# Main.net
KiCad netlist of a schematic drawn in Altium Designer
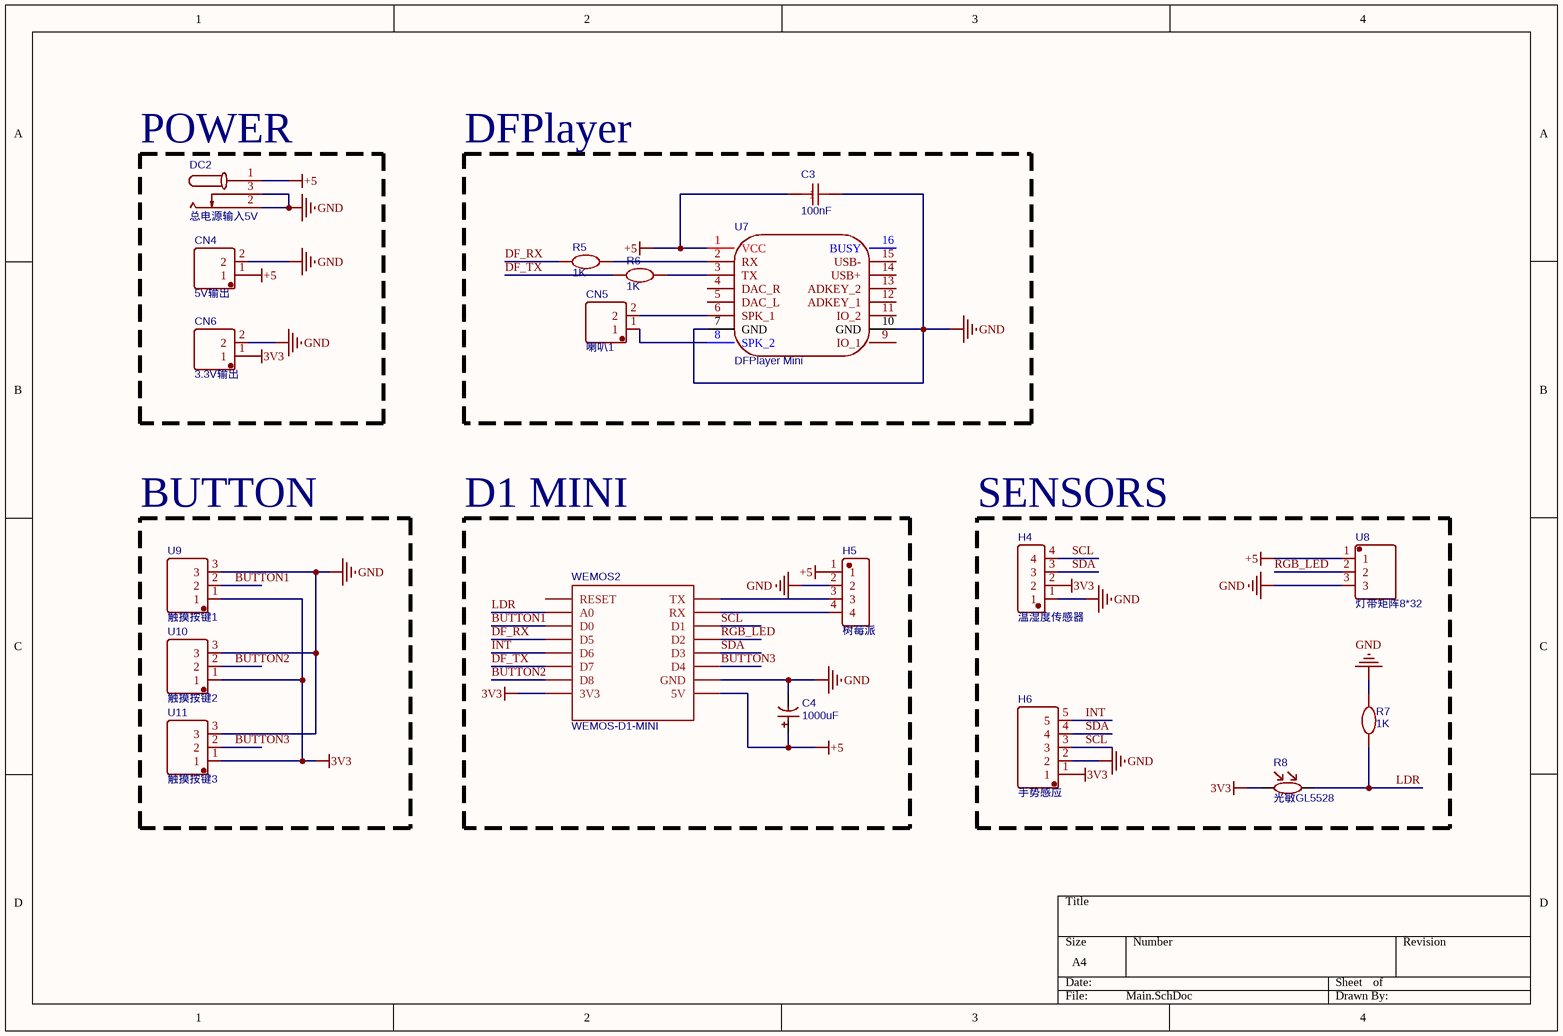
[diagram p0: Main.SchDoc]

(export (version "E")
  (design (tool "Eeschema 10.0.6"))
  (components
    (comp (ref "C3")
      (value "100nF")
      (footprint "CAP-SMD_BD6.3-L6.6-W6.6-LS7.2-FD")
      (fields
        (field (name "BOM_SUPPLIER PART") "C386152")
        (field (name "BOM_MANUFACTURER PART") "UMK107B104KAHT")
        (field (name "CONTRIBUTOR") "LCSC")
      )
      (libsource (lib "Connecter") (part "100nF"))
    )
    (comp (ref "C4")
      (value "1000uF")
      (footprint "1000uf25v")
      (fields (field (name "BOM_MANUFACTURER PART") "1000uF 16V") (field (name "BOM_SUPPLIER PART") "C43909"))
      (libsource (lib "Connecter") (part "1000uF"))
    )
    (comp (ref "CN4")
      (value "5V输出")
      (footprint "HDR-TH_2P-P2.54-V")
      (fields (field (name "BOM_SUPPLIER PART") "C160332") (field (name "CONTRIBUTOR") "LCSC"))
      (libsource (lib "Connecter") (part "5V输出"))
    )
    (comp (ref "CN5")
      (value "喇叭1")
      (footprint "HDR-TH_2P-P2.54-V")
      (fields (field (name "BOM_SUPPLIER PART") "C160332") (field (name "CONTRIBUTOR") "LCSC"))
      (libsource (lib "Connecter") (part "喇叭1"))
    )
    (comp (ref "CN6")
      (value "3.3V输出")
      (footprint "HDR-TH_2P-P2.54-V")
      (fields (field (name "BOM_SUPPLIER PART") "C160332") (field (name "CONTRIBUTOR") "LCSC"))
      (libsource (lib "Connecter") (part "3.3V输出"))
    )
    (comp (ref "DC2")
      (value "总电源输入5V")
      (footprint "DC-IN-TH_DC005")
      (fields (field (name "BOM_SUPPLIER PART") "C132516") (field (name "CONTRIBUTOR") "LCSC"))
      (libsource (lib "Connecter") (part "总电源输入5V"))
    )
    (comp (ref "H4")
      (value "温湿度传感器")
      (footprint "HDR-TH_4P-P2.54-V")
      (fields
        (field (name "BOM_MANUFACTURER PART") "Z-211-0411-0021-001")
        (field (name "BOM_SUPPLIER PART") "C152150")
        (field (name "CONTRIBUTOR") "LCSC")
      )
      (libsource (lib "Connecter") (part "i2C"))
    )
    (comp (ref "H5")
      (value "树莓派")
      (footprint "HDR-TH_4P-P2.54-V")
      (fields
        (field (name "BOM_MANUFACTURER PART") "Z-211-0411-0021-001")
        (field (name "BOM_SUPPLIER PART") "C152150")
        (field (name "CONTRIBUTOR") "LCSC")
      )
      (libsource (lib "Connecter") (part "树莓派"))
    )
    (comp (ref "H6")
      (value "手势感应")
      (footprint "HDR-TH_5P-P2.54-V")
      (fields
        (field (name "BOM_SUPPLIER PART") "C180219")
        (field (name "BOM_MANUFACTURER PART") "77311-462K05LF")
        (field (name "CONTRIBUTOR") "LCSC")
      )
      (libsource (lib "Connecter") (part "手势感应"))
    )
    (comp (ref "R5")
      (value "1K")
      (footprint "0805_R")
      (fields
        (field (name "BOM_SUPPLIER PART") "C433503")
        (field (name "BOM_MANUFACTURER PART") "RN 1/8W 1K F T/B A1")
        (field (name "CONTRIBUTOR") "LCSC")
      )
      (libsource (lib "Connecter") (part "1K"))
    )
    (comp (ref "R6")
      (value "1K")
      (footprint "0805_R")
      (fields
        (field (name "BOM_SUPPLIER PART") "C433503")
        (field (name "BOM_MANUFACTURER PART") "RN 1/8W 1K F T/B A1")
        (field (name "CONTRIBUTOR") "LCSC")
      )
      (libsource (lib "Connecter") (part "1K"))
    )
    (comp (ref "R7")
      (value "1K")
      (footprint "0805_R")
      (fields
        (field (name "BOM_SUPPLIER PART") "C433503")
        (field (name "BOM_MANUFACTURER PART") "RN 1/8W 1K F T/B A1")
        (field (name "CONTRIBUTOR") "LCSC")
      )
      (libsource (lib "Connecter") (part "1K"))
    )
    (comp (ref "R8")
      (value "光敏GL5528")
      (footprint "RES-TH_L5.1-W4.3-P3.40-D0.5")
      (fields (field (name "BOM_MANUFACTURER PART") "GL5528") (field (name "BOM_SUPPLIER PART") "C125627"))
      (libsource (lib "Connecter") (part "光敏GL5528"))
    )
    (comp (ref "U7")
      (value "DFPlayer Mini")
      (footprint "DFPLAYER MINI")
      (fields (field (name "CONTRIBUTOR") "adrirobot"))
      (libsource (lib "Connecter") (part "DFPlayer Mini"))
    )
    (comp (ref "U8")
      (value "灯带矩阵8*32")
      (footprint "HDR-TH_3P-P2.54-V")
      (fields
        (field (name "BOM_SUPPLIER PART") "C265013")
        (field (name "BOM_MANUFACTURER PART") "RE-H032TD-1130")
        (field (name "CONTRIBUTOR") "LCSC")
      )
      (libsource (lib "Connecter") (part "灯带矩阵8*32"))
    )
    (comp (ref "U9")
      (value "触摸按键1")
      (footprint "HDR-TH_3P-P2.54-V")
      (fields
        (field (name "BOM_SUPPLIER PART") "C265013")
        (field (name "BOM_MANUFACTURER PART") "RE-H032TD-1130")
        (field (name "CONTRIBUTOR") "LCSC")
      )
      (libsource (lib "Connecter") (part "触摸按键1"))
    )
    (comp (ref "U10")
      (value "触摸按键2")
      (footprint "HDR-TH_3P-P2.54-V")
      (fields
        (field (name "BOM_SUPPLIER PART") "C265013")
        (field (name "BOM_MANUFACTURER PART") "RE-H032TD-1130")
        (field (name "CONTRIBUTOR") "LCSC")
      )
      (libsource (lib "Connecter") (part "触摸按键2"))
    )
    (comp (ref "U11")
      (value "触摸按键3")
      (footprint "HDR-TH_3P-P2.54-V")
      (fields
        (field (name "BOM_SUPPLIER PART") "C265013")
        (field (name "BOM_MANUFACTURER PART") "RE-H032TD-1130")
        (field (name "CONTRIBUTOR") "LCSC")
      )
      (libsource (lib "Connecter") (part "触摸按键3"))
    )
    (comp (ref "WEMOS2")
      (value "WEMOS-D1-MINI")
      (footprint "WEMOS_D1_MINI_V2.3.0")
      (libsource (lib "Connecter") (part "WEMOS-D1-MINI"))
    )
  )
  (nets
    (net (code "1") (name "+5") (class "Default")
      (node (ref "C3") (pin "1") (pinfunction "1_1") (pintype "passive"))
      (node (ref "C4") (pin "1") (pinfunction "1_1") (pintype "passive"))
      (node (ref "CN4") (pin "1") (pinfunction "1_1") (pintype "passive"))
      (node (ref "DC2") (pin "1") (pinfunction "1_1") (pintype "passive"))
      (node (ref "H5") (pin "1") (pinfunction "1_1") (pintype "passive"))
      (node (ref "U7") (pin "1") (pinfunction "VCC_1") (pintype "passive"))
      (node (ref "U8") (pin "1") (pinfunction "1_1") (pintype "passive"))
      (node (ref "WEMOS2") (pin "5V") (pinfunction "5V_5V") (pintype "passive"))
    )
    (net (code "2") (name "/BUTTON1") (class "Default")
      (node (ref "U9") (pin "2") (pinfunction "2_2") (pintype "passive"))
      (node (ref "WEMOS2") (pin "D0") (pinfunction "D0_D0") (pintype "passive"))
    )
    (net (code "3") (name "/BUTTON2") (class "Default")
      (node (ref "U10") (pin "2") (pinfunction "2_2") (pintype "passive"))
      (node (ref "WEMOS2") (pin "D8") (pinfunction "D8_D8") (pintype "passive"))
    )
    (net (code "4") (name "/BUTTON3") (class "Default")
      (node (ref "U11") (pin "2") (pinfunction "2_2") (pintype "passive"))
      (node (ref "WEMOS2") (pin "D4") (pinfunction "D4_D4") (pintype "passive"))
    )
    (net (code "5") (name "/DF_RX") (class "Default")
      (node (ref "R5") (pin "1") (pinfunction "1_1") (pintype "passive"))
      (node (ref "WEMOS2") (pin "D5") (pinfunction "D5_D5") (pintype "passive"))
    )
    (net (code "6") (name "/DF_TX") (class "Default")
      (node (ref "R6") (pin "1") (pinfunction "1_1") (pintype "passive"))
      (node (ref "WEMOS2") (pin "D7") (pinfunction "D7_D7") (pintype "passive"))
    )
    (net (code "7") (name "/INT") (class "Default")
      (node (ref "H6") (pin "5") (pinfunction "5_5") (pintype "passive"))
      (node (ref "WEMOS2") (pin "D6") (pinfunction "D6_D6") (pintype "passive"))
    )
    (net (code "8") (name "/LDR") (class "Default")
      (node (ref "R7") (pin "1") (pinfunction "1_1") (pintype "passive"))
      (node (ref "R8") (pin "2") (pinfunction "2_2") (pintype "passive"))
      (node (ref "WEMOS2") (pin "A0") (pinfunction "A0_A0") (pintype "passive"))
    )
    (net (code "9") (name "/RGB_LED") (class "Default")
      (node (ref "U8") (pin "2") (pinfunction "2_2") (pintype "passive"))
      (node (ref "WEMOS2") (pin "D2") (pinfunction "D2_D2") (pintype "passive"))
    )
    (net (code "10") (name "/SCL") (class "Default")
      (node (ref "H4") (pin "4") (pinfunction "4_4") (pintype "passive"))
      (node (ref "H6") (pin "3") (pinfunction "3_3") (pintype "passive"))
      (node (ref "WEMOS2") (pin "D1") (pinfunction "D1_D1") (pintype "passive"))
    )
    (net (code "11") (name "/SDA") (class "Default")
      (node (ref "H4") (pin "3") (pinfunction "3_3") (pintype "passive"))
      (node (ref "H6") (pin "4") (pinfunction "4_4") (pintype "passive"))
      (node (ref "WEMOS2") (pin "D3") (pinfunction "D3_D3") (pintype "passive"))
    )
    (net (code "12") (name "3V3") (class "Default")
      (node (ref "CN6") (pin "1") (pinfunction "1_1") (pintype "passive"))
      (node (ref "H4") (pin "2") (pinfunction "2_2") (pintype "passive"))
      (node (ref "H6") (pin "1") (pinfunction "1_1") (pintype "passive"))
      (node (ref "R8") (pin "1") (pinfunction "1_1") (pintype "passive"))
      (node (ref "U10") (pin "1") (pinfunction "1_1") (pintype "passive"))
      (node (ref "U11") (pin "1") (pinfunction "1_1") (pintype "passive"))
      (node (ref "U9") (pin "1") (pinfunction "1_1") (pintype "passive"))
      (node (ref "WEMOS2") (pin "3V3") (pinfunction "3V3_3V3") (pintype "passive"))
    )
    (net (code "13") (name "GND") (class "Default")
      (node (ref "C3") (pin "2") (pinfunction "2_2") (pintype "passive"))
      (node (ref "C4") (pin "2") (pinfunction "2_2") (pintype "passive"))
      (node (ref "CN4") (pin "2") (pinfunction "2_2") (pintype "passive"))
      (node (ref "CN6") (pin "2") (pinfunction "2_2") (pintype "passive"))
      (node (ref "DC2") (pin "2") (pinfunction "2_2") (pintype "passive"))
      (node (ref "DC2") (pin "3") (pinfunction "3_3") (pintype "passive"))
      (node (ref "H4") (pin "1") (pinfunction "1_1") (pintype "passive"))
      (node (ref "H5") (pin "2") (pinfunction "2_2") (pintype "passive"))
      (node (ref "H6") (pin "2") (pinfunction "2_2") (pintype "passive"))
      (node (ref "R7") (pin "2") (pinfunction "2_2") (pintype "passive"))
      (node (ref "U10") (pin "3") (pinfunction "3_3") (pintype "passive"))
      (node (ref "U11") (pin "3") (pinfunction "3_3") (pintype "passive"))
      (node (ref "U7") (pin "10") (pinfunction "GND_10") (pintype "passive"))
      (node (ref "U7") (pin "7") (pinfunction "GND_7") (pintype "passive"))
      (node (ref "U8") (pin "3") (pinfunction "3_3") (pintype "passive"))
      (node (ref "U9") (pin "3") (pinfunction "3_3") (pintype "passive"))
      (node (ref "WEMOS2") (pin "GND") (pinfunction "GND_GND") (pintype "passive"))
    )
    (net (code "14") (name "Net-(H5-Pad3)") (class "Default")
      (node (ref "H5") (pin "3") (pinfunction "3_3") (pintype "passive"))
      (node (ref "WEMOS2") (pin "TX") (pinfunction "TX_TX") (pintype "passive"))
    )
    (net (code "15") (name "Net-(H5-Pad4)") (class "Default")
      (node (ref "H5") (pin "4") (pinfunction "4_4") (pintype "passive"))
      (node (ref "WEMOS2") (pin "RX") (pinfunction "RX_RX") (pintype "passive"))
    )
    (net (code "16") (name "Net-(U7-RX)") (class "Default")
      (node (ref "R5") (pin "2") (pinfunction "2_2") (pintype "passive"))
      (node (ref "U7") (pin "2") (pinfunction "RX_2") (pintype "passive"))
    )
    (net (code "17") (name "Net-(U7-SPK_1)") (class "Default")
      (node (ref "CN5") (pin "2") (pinfunction "2_2") (pintype "passive"))
      (node (ref "U7") (pin "6") (pinfunction "SPK_1_6") (pintype "passive"))
    )
    (net (code "18") (name "Net-(U7-SPK_2)") (class "Default")
      (node (ref "CN5") (pin "1") (pinfunction "1_1") (pintype "passive"))
      (node (ref "U7") (pin "8") (pinfunction "SPK_2_8") (pintype "passive"))
    )
    (net (code "19") (name "Net-(U7-TX)") (class "Default")
      (node (ref "R6") (pin "2") (pinfunction "2_2") (pintype "passive"))
      (node (ref "U7") (pin "3") (pinfunction "TX_3") (pintype "passive"))
    )
    (net (code "20") (name "unconnected-(U7-ADKEY_1-Pad12)") (class "Default")
      (node (ref "U7") (pin "12") (pinfunction "ADKEY_1_12") (pintype "passive"))
    )
    (net (code "21") (name "unconnected-(U7-ADKEY_2-Pad13)") (class "Default")
      (node (ref "U7") (pin "13") (pinfunction "ADKEY_2_13") (pintype "passive"))
    )
    (net (code "22") (name "unconnected-(U7-BUSY-Pad16)") (class "Default")
      (node (ref "U7") (pin "16") (pinfunction "BUSY_16") (pintype "passive"))
    )
    (net (code "23") (name "unconnected-(U7-DAC_L-Pad5)") (class "Default")
      (node (ref "U7") (pin "5") (pinfunction "DAC_L_5") (pintype "passive"))
    )
    (net (code "24") (name "unconnected-(U7-DAC_R-Pad4)") (class "Default")
      (node (ref "U7") (pin "4") (pinfunction "DAC_R_4") (pintype "passive"))
    )
    (net (code "25") (name "unconnected-(U7-IO_1-Pad9)") (class "Default")
      (node (ref "U7") (pin "9") (pinfunction "IO_1_9") (pintype "passive"))
    )
    (net (code "26") (name "unconnected-(U7-IO_2-Pad11)") (class "Default")
      (node (ref "U7") (pin "11") (pinfunction "IO_2_11") (pintype "passive"))
    )
    (net (code "27") (name "unconnected-(U7-USB+-Pad14)") (class "Default")
      (node (ref "U7") (pin "14") (pinfunction "USB+_14") (pintype "passive"))
    )
    (net (code "28") (name "unconnected-(U7-USB--Pad15)") (class "Default")
      (node (ref "U7") (pin "15") (pinfunction "USB-_15") (pintype "passive"))
    )
    (net (code "29") (name "unconnected-(WEMOS2-PadRESET)") (class "Default")
      (node (ref "WEMOS2") (pin "RESET") (pinfunction "RESET_RESET") (pintype "passive"))
    )
  )
)
